# schematic_LED.net
KiCad netlist of a schematic drawn in Altium Designer
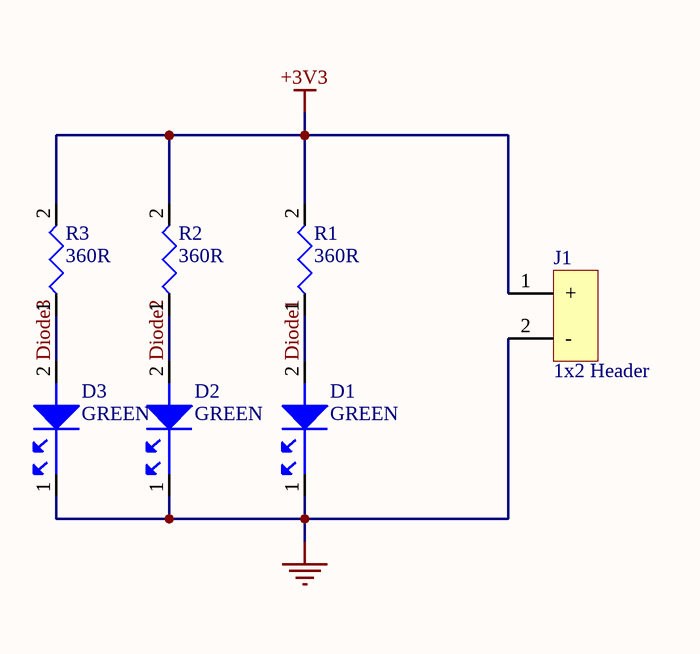
[diagram p0: schematic_LED.SchDoc]

(export (version "E")
  (design (tool "Eeschema 10.0.6"))
  (components
    (comp (ref "D1")
      (value "GREEN")
      (footprint "LED0603G")
      (description "LED GREEN ESS II SMD")
      (fields
        (field (name "MANUFACTURER") "Panasonic SSG")
        (field (name "MANUFACTURER PART NUMBER") "LNJ337W83RA")
      )
      (libsource (lib "Schlib1") (part "LNJ337W83RA"))
    )
    (comp (ref "D2")
      (value "GREEN")
      (footprint "LED0603G")
      (description "LED GREEN ESS II SMD")
      (fields
        (field (name "MANUFACTURER") "Panasonic SSG")
        (field (name "MANUFACTURER PART NUMBER") "LNJ337W83RA")
      )
      (libsource (lib "Schlib1") (part "LNJ337W83RA"))
    )
    (comp (ref "D3")
      (value "GREEN")
      (footprint "LED0603G")
      (description "LED GREEN ESS II SMD")
      (fields
        (field (name "MANUFACTURER") "Panasonic SSG")
        (field (name "MANUFACTURER PART NUMBER") "LNJ337W83RA")
      )
      (libsource (lib "Schlib1") (part "LNJ337W83RA"))
    )
    (comp (ref "J1")
      (value "1x2 Header")
      (footprint "HDR1X2")
      (description "Conn Wire to Board HDR 2 POS 2.54mm Solder ST Thru-Hole Bag")
      (fields (field (name "MANUFACTURER") "Molex") (field (name "MANUFACTURER PART NUMBER") "22-29-2021"))
      (libsource (lib "Schlib1") (part "22-29-2021"))
    )
    (comp (ref "R1")
      (value "360R")
      (footprint "R0805")
      (description "Res Thick Film 0805 360 Ohm 1% 0.125W(1/8W) ±100ppm/C Molded SMD Automotive Paper T/R")
      (fields
        (field (name "MANUFACTURER") "Vishay")
        (field (name "MANUFACTURER PART NUMBER") "CRCW0805360RFKEA")
      )
      (libsource (lib "Schlib1") (part "CRCW0805360RFKEA"))
    )
    (comp (ref "R2")
      (value "360R")
      (footprint "R0805")
      (description "Res Thick Film 0805 360 Ohm 1% 0.125W(1/8W) ±100ppm/C Molded SMD Automotive Paper T/R")
      (fields
        (field (name "MANUFACTURER") "Vishay")
        (field (name "MANUFACTURER PART NUMBER") "CRCW0805360RFKEA")
      )
      (libsource (lib "Schlib1") (part "CRCW0805360RFKEA"))
    )
    (comp (ref "R3")
      (value "360R")
      (footprint "R0805")
      (description "Res Thick Film 0805 360 Ohm 1% 0.125W(1/8W) ±100ppm/C Molded SMD Automotive Paper T/R")
      (fields
        (field (name "MANUFACTURER") "Vishay")
        (field (name "MANUFACTURER PART NUMBER") "CRCW0805360RFKEA")
      )
      (libsource (lib "Schlib1") (part "CRCW0805360RFKEA"))
    )
  )
  (nets
    (net (code "1") (name "+3V3") (class "Default")
      (node (ref "J1") (pin "1") (pinfunction "+_1") (pintype "passive"))
      (node (ref "R1") (pin "2") (pinfunction "2_2") (pintype "passive"))
      (node (ref "R2") (pin "2") (pinfunction "2_2") (pintype "passive"))
      (node (ref "R3") (pin "2") (pinfunction "2_2") (pintype "passive"))
    )
    (net (code "2") (name "/Diode1") (class "Default")
      (node (ref "D1") (pin "2") (pinfunction "2_2") (pintype "passive"))
      (node (ref "R1") (pin "1") (pinfunction "1_1") (pintype "passive"))
    )
    (net (code "3") (name "/Diode2") (class "Default")
      (node (ref "D2") (pin "2") (pinfunction "2_2") (pintype "passive"))
      (node (ref "R2") (pin "1") (pinfunction "1_1") (pintype "passive"))
    )
    (net (code "4") (name "/Diode3") (class "Default")
      (node (ref "D3") (pin "2") (pinfunction "2_2") (pintype "passive"))
      (node (ref "R3") (pin "1") (pinfunction "1_1") (pintype "passive"))
    )
    (net (code "5") (name "GND") (class "Default")
      (node (ref "D1") (pin "1") (pinfunction "1_1") (pintype "passive"))
      (node (ref "D2") (pin "1") (pinfunction "1_1") (pintype "passive"))
      (node (ref "D3") (pin "1") (pinfunction "1_1") (pintype "passive"))
      (node (ref "J1") (pin "2") (pinfunction "-_2") (pintype "passive"))
    )
  )
)
